# MCU.net
KiCad netlist of a schematic drawn in EAGLE
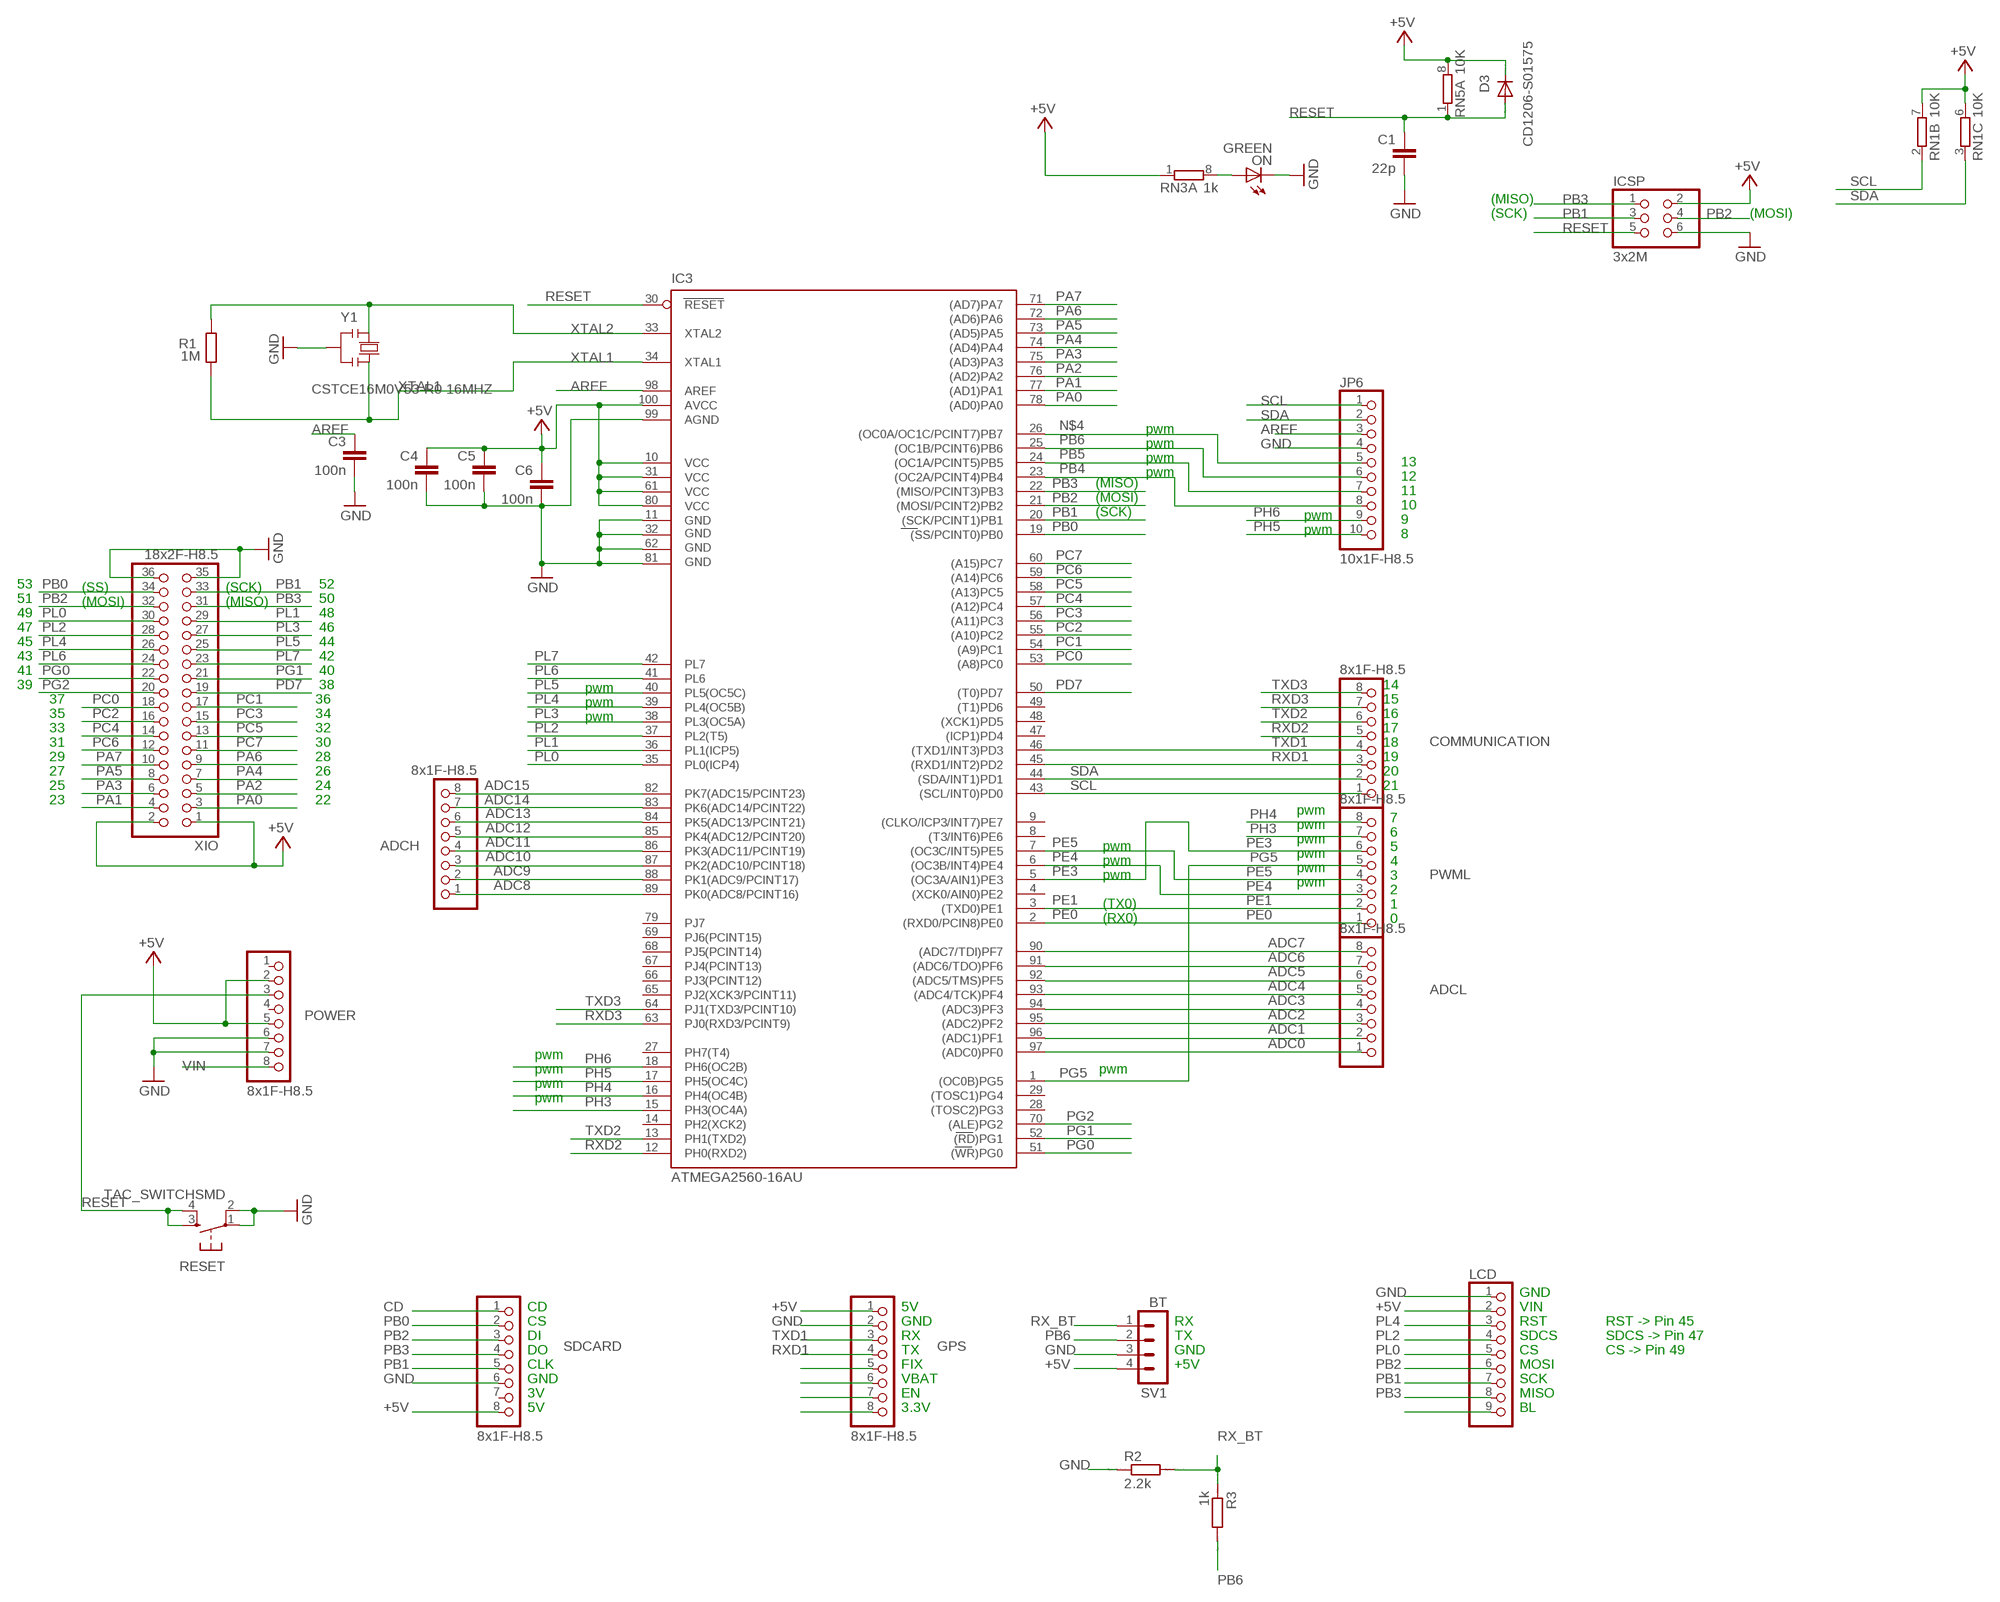
[diagram p0: schematic, sheet 1]

(export (version "E")
  (design (tool "Eeschema 10.0.6"))
  (components
    (comp (ref "ADCH")
      (value "8x1F-H8.5")
      (footprint "eagle-import:1X08")
      (libsource (lib "eagle-import") (part "PINHD-1X8"))
    )
    (comp (ref "ADCL")
      (value "8x1F-H8.5")
      (footprint "eagle-import:1X08")
      (libsource (lib "eagle-import") (part "PINHD-1X8"))
    )
    (comp (ref "C1")
      (value "22p")
      (footprint "eagle-import:C0603-ROUND")
      (libsource (lib "eagle-import") (part "C-EU0603-RND"))
    )
    (comp (ref "C3")
      (value "100n")
      (footprint "eagle-import:C0603-ROUND")
      (libsource (lib "eagle-import") (part "C-EU0603-RND"))
    )
    (comp (ref "C4")
      (value "100n")
      (footprint "eagle-import:C0603-ROUND")
      (libsource (lib "eagle-import") (part "C-EU0603-RND"))
    )
    (comp (ref "C5")
      (value "100n")
      (footprint "eagle-import:C0603-ROUND")
      (libsource (lib "eagle-import") (part "C-EU0603-RND"))
    )
    (comp (ref "C6")
      (value "100n")
      (footprint "eagle-import:C0603-ROUND")
      (libsource (lib "eagle-import") (part "C-EU0603-RND"))
    )
    (comp (ref "COMMUNICATION")
      (value "8x1F-H8.5")
      (footprint "eagle-import:1X08")
      (libsource (lib "eagle-import") (part "PINHD-1X8"))
    )
    (comp (ref "D3")
      (value "CD1206-S01575")
      (footprint "eagle-import:MINIMELF")
      (libsource (lib "eagle-import") (part "DIODE-MINIMELF"))
    )
    (comp (ref "GPS")
      (value "8x1F-H8.5")
      (footprint "eagle-import:1X08")
      (libsource (lib "eagle-import") (part "PINHD-1X8"))
    )
    (comp (ref "IC3")
      (value "ATMEGA2560-16AU")
      (footprint "eagle-import:TQFP100")
      (libsource (lib "eagle-import") (part "ATMEGA2560AU2560-16"))
    )
    (comp (ref "ICSP")
      (value "3x2M")
      (footprint "eagle-import:2X03")
      (libsource (lib "eagle-import") (part "PINHD-2X3"))
    )
    (comp (ref "JP6")
      (value "10x1F-H8.5")
      (footprint "eagle-import:1X10")
      (libsource (lib "eagle-import") (part "PINHD-1X10_ARD"))
    )
    (comp (ref "LCD")
      (value "PINHD-1X9")
      (footprint "eagle-import:1X09")
      (libsource (lib "eagle-import") (part "PINHD-1X9"))
    )
    (comp (ref "ON")
      (value "GREEN")
      (footprint "eagle-import:CHIP-LED0805")
      (libsource (lib "eagle-import") (part "LEDCHIP-LED0805"))
    )
    (comp (ref "POWER")
      (value "8x1F-H8.5")
      (footprint "eagle-import:1X08")
      (libsource (lib "eagle-import") (part "PINHD-1X8"))
    )
    (comp (ref "PWML")
      (value "8x1F-H8.5")
      (footprint "eagle-import:1X08")
      (libsource (lib "eagle-import") (part "PINHD-1X8"))
    )
    (comp (ref "R1")
      (value "1M")
      (footprint "eagle-import:R0603-ROUND")
      (libsource (lib "eagle-import") (part "R-EU_R0603"))
    )
    (comp (ref "R2")
      (value "2.2k")
      (footprint "eagle-import:R0603")
      (libsource (lib "eagle-import") (part "resistor_R-EU_R0603"))
    )
    (comp (ref "R3")
      (value "1k")
      (footprint "eagle-import:R0603")
      (libsource (lib "eagle-import") (part "resistor_R-EU_R0603"))
    )
    (comp (ref "RESET")
      (value "TAC_SWITCHSMD")
      (footprint "eagle-import:TACTILE-SWITCH-SMD")
      (libsource (lib "eagle-import") (part "TAC_SWITCHSMD"))
    )
    (comp (ref "RN1")
      (value "10K")
      (footprint "eagle-import:CAT16")
      (libsource (lib "eagle-import") (part "4R-NCAT16"))
    )
    (comp (ref "RN3")
      (value "1k")
      (footprint "eagle-import:CAY16")
      (libsource (lib "eagle-import") (part "4R-NCAY16"))
    )
    (comp (ref "RN5")
      (value "10K")
      (footprint "eagle-import:CAT16")
      (libsource (lib "eagle-import") (part "4R-NCAT16"))
    )
    (comp (ref "SDCARD")
      (value "8x1F-H8.5")
      (footprint "eagle-import:1X08")
      (libsource (lib "eagle-import") (part "PINHD-1X8"))
    )
    (comp (ref "SV1")
      (value "BT")
      (footprint "eagle-import:MA04-1")
      (libsource (lib "eagle-import") (part "MA04-1"))
    )
    (comp (ref "XIO")
      (value "18x2F-H8.5")
      (footprint "eagle-import:2X18")
      (libsource (lib "eagle-import") (part "PINHD-2X18"))
    )
    (comp (ref "Y1")
      (value "CSTCE16M0V53-R0 16MHZ")
      (footprint "eagle-import:RESONATOR")
      (libsource (lib "eagle-import") (part "RESONATORMU"))
    )
  )
  (nets
    (net (code "1") (name "+5V") (class "Default")
      (node (ref "C4") (pin "1") (pinfunction "1_1") (pintype "passive"))
      (node (ref "C5") (pin "1") (pinfunction "1_1") (pintype "passive"))
      (node (ref "C6") (pin "1") (pinfunction "1_1") (pintype "passive"))
      (node (ref "D3") (pin "C") (pinfunction "C_C") (pintype "passive"))
      (node (ref "GPS") (pin "1") (pinfunction "1_1") (pintype "passive"))
      (node (ref "IC3") (pin "10") (pinfunction "VCC_10") (pintype "power_in"))
      (node (ref "IC3") (pin "100") (pinfunction "AVCC_100") (pintype "power_in"))
      (node (ref "IC3") (pin "31") (pinfunction "VCC1_31") (pintype "power_in"))
      (node (ref "IC3") (pin "61") (pinfunction "VCC2_61") (pintype "power_in"))
      (node (ref "IC3") (pin "80") (pinfunction "VCC3_80") (pintype "power_in"))
      (node (ref "ICSP") (pin "2") (pinfunction "2_2") (pintype "passive"))
      (node (ref "LCD") (pin "2") (pinfunction "2_2") (pintype "passive"))
      (node (ref "POWER") (pin "2") (pinfunction "2_2") (pintype "passive"))
      (node (ref "POWER") (pin "5") (pinfunction "5_5") (pintype "passive"))
      (node (ref "RN1") (pin "6") (pinfunction "2_6") (pintype "passive"))
      (node (ref "RN1") (pin "7") (pinfunction "2_7") (pintype "passive"))
      (node (ref "RN3") (pin "1") (pinfunction "1_1") (pintype "passive"))
      (node (ref "RN5") (pin "8") (pinfunction "2_8") (pintype "passive"))
      (node (ref "SDCARD") (pin "8") (pinfunction "8_8") (pintype "passive"))
      (node (ref "SV1") (pin "4") (pinfunction "4_4") (pintype "passive"))
      (node (ref "XIO") (pin "1") (pinfunction "1_1") (pintype "passive"))
      (node (ref "XIO") (pin "2") (pinfunction "2_2") (pintype "passive"))
    )
    (net (code "2") (name "/ADC0") (class "Default")
      (node (ref "ADCL") (pin "1") (pinfunction "1_1") (pintype "passive"))
      (node (ref "IC3") (pin "97") (pinfunction "(ADC0)PF0_97") (pintype "bidirectional"))
    )
    (net (code "3") (name "/ADC1") (class "Default")
      (node (ref "ADCL") (pin "2") (pinfunction "2_2") (pintype "passive"))
      (node (ref "IC3") (pin "96") (pinfunction "(ADC1)PF1_96") (pintype "bidirectional"))
    )
    (net (code "4") (name "/ADC2") (class "Default")
      (node (ref "ADCL") (pin "3") (pinfunction "3_3") (pintype "passive"))
      (node (ref "IC3") (pin "95") (pinfunction "(ADC2)PF2_95") (pintype "bidirectional"))
    )
    (net (code "5") (name "/ADC3") (class "Default")
      (node (ref "ADCL") (pin "4") (pinfunction "4_4") (pintype "passive"))
      (node (ref "IC3") (pin "94") (pinfunction "(ADC3)PF3_94") (pintype "bidirectional"))
    )
    (net (code "6") (name "/ADC4") (class "Default")
      (node (ref "ADCL") (pin "5") (pinfunction "5_5") (pintype "passive"))
      (node (ref "IC3") (pin "93") (pinfunction "(ADC4/TCK)PF4_93") (pintype "bidirectional"))
    )
    (net (code "7") (name "/ADC5") (class "Default")
      (node (ref "ADCL") (pin "6") (pinfunction "6_6") (pintype "passive"))
      (node (ref "IC3") (pin "92") (pinfunction "(ADC5/TMS)PF5_92") (pintype "bidirectional"))
    )
    (net (code "8") (name "/ADC6") (class "Default")
      (node (ref "ADCL") (pin "7") (pinfunction "7_7") (pintype "passive"))
      (node (ref "IC3") (pin "91") (pinfunction "(ADC6/TDO)PF6_91") (pintype "bidirectional"))
    )
    (net (code "9") (name "/ADC7") (class "Default")
      (node (ref "ADCL") (pin "8") (pinfunction "8_8") (pintype "passive"))
      (node (ref "IC3") (pin "90") (pinfunction "(ADC7/TDI)PF7_90") (pintype "bidirectional"))
    )
    (net (code "10") (name "/ADC8") (class "Default")
      (node (ref "ADCH") (pin "1") (pinfunction "1_1") (pintype "passive"))
      (node (ref "IC3") (pin "89") (pinfunction "PK0(ADC8/PCINT16)_89") (pintype "bidirectional"))
    )
    (net (code "11") (name "/ADC9") (class "Default")
      (node (ref "ADCH") (pin "2") (pinfunction "2_2") (pintype "passive"))
      (node (ref "IC3") (pin "88") (pinfunction "PK1(ADC9/PCINT17)_88") (pintype "bidirectional"))
    )
    (net (code "12") (name "/ADC10") (class "Default")
      (node (ref "ADCH") (pin "3") (pinfunction "3_3") (pintype "passive"))
      (node (ref "IC3") (pin "87") (pinfunction "PK2(ADC10/PCINT18)_87") (pintype "bidirectional"))
    )
    (net (code "13") (name "/ADC11") (class "Default")
      (node (ref "ADCH") (pin "4") (pinfunction "4_4") (pintype "passive"))
      (node (ref "IC3") (pin "86") (pinfunction "PK3(ADC11/PCINT19)_86") (pintype "bidirectional"))
    )
    (net (code "14") (name "/ADC12") (class "Default")
      (node (ref "ADCH") (pin "5") (pinfunction "5_5") (pintype "passive"))
      (node (ref "IC3") (pin "85") (pinfunction "PK4(ADC12/PCINT20)_85") (pintype "bidirectional"))
    )
    (net (code "15") (name "/ADC13") (class "Default")
      (node (ref "ADCH") (pin "6") (pinfunction "6_6") (pintype "passive"))
      (node (ref "IC3") (pin "84") (pinfunction "PK5(ADC13/PCINT21)_84") (pintype "bidirectional"))
    )
    (net (code "16") (name "/ADC14") (class "Default")
      (node (ref "ADCH") (pin "7") (pinfunction "7_7") (pintype "passive"))
      (node (ref "IC3") (pin "83") (pinfunction "PK6(ADC14/PCINT22)_83") (pintype "bidirectional"))
    )
    (net (code "17") (name "/ADC15") (class "Default")
      (node (ref "ADCH") (pin "8") (pinfunction "8_8") (pintype "passive"))
      (node (ref "IC3") (pin "82") (pinfunction "PK7(ADC15/PCINT23)_82") (pintype "bidirectional"))
    )
    (net (code "18") (name "/AREF") (class "Default")
      (node (ref "C3") (pin "1") (pinfunction "1_1") (pintype "passive"))
      (node (ref "IC3") (pin "98") (pinfunction "AREF_98") (pintype "bidirectional"))
      (node (ref "JP6") (pin "3") (pinfunction "3_3") (pintype "passive"))
    )
    (net (code "19") (name "/CD") (class "Default")
      (node (ref "SDCARD") (pin "1") (pinfunction "1_1") (pintype "passive"))
    )
    (net (code "20") (name "/N$4") (class "Default")
      (node (ref "IC3") (pin "26") (pinfunction "(OC0A/OC1C/PCINT7)PB7_26") (pintype "bidirectional"))
      (node (ref "JP6") (pin "5") (pinfunction "5_5") (pintype "passive"))
    )
    (net (code "21") (name "/PA0") (class "Default")
      (node (ref "IC3") (pin "78") (pinfunction "(AD0)PA0_78") (pintype "bidirectional"))
      (node (ref "XIO") (pin "3") (pinfunction "3_3") (pintype "passive"))
    )
    (net (code "22") (name "/PA1") (class "Default")
      (node (ref "IC3") (pin "77") (pinfunction "(AD1)PA1_77") (pintype "bidirectional"))
      (node (ref "XIO") (pin "4") (pinfunction "4_4") (pintype "passive"))
    )
    (net (code "23") (name "/PA2") (class "Default")
      (node (ref "IC3") (pin "76") (pinfunction "(AD2)PA2_76") (pintype "bidirectional"))
      (node (ref "XIO") (pin "5") (pinfunction "5_5") (pintype "passive"))
    )
    (net (code "24") (name "/PA3") (class "Default")
      (node (ref "IC3") (pin "75") (pinfunction "(AD3)PA3_75") (pintype "bidirectional"))
      (node (ref "XIO") (pin "6") (pinfunction "6_6") (pintype "passive"))
    )
    (net (code "25") (name "/PA4") (class "Default")
      (node (ref "IC3") (pin "74") (pinfunction "(AD4)PA4_74") (pintype "bidirectional"))
      (node (ref "XIO") (pin "7") (pinfunction "7_7") (pintype "passive"))
    )
    (net (code "26") (name "/PA5") (class "Default")
      (node (ref "IC3") (pin "73") (pinfunction "(AD5)PA5_73") (pintype "bidirectional"))
      (node (ref "XIO") (pin "8") (pinfunction "8_8") (pintype "passive"))
    )
    (net (code "27") (name "/PA6") (class "Default")
      (node (ref "IC3") (pin "72") (pinfunction "(AD6)PA6_72") (pintype "bidirectional"))
      (node (ref "XIO") (pin "9") (pinfunction "9_9") (pintype "passive"))
    )
    (net (code "28") (name "/PA7") (class "Default")
      (node (ref "IC3") (pin "71") (pinfunction "(AD7)PA7_71") (pintype "bidirectional"))
      (node (ref "XIO") (pin "10") (pinfunction "10_10") (pintype "passive"))
    )
    (net (code "29") (name "/PB0") (class "Default")
      (node (ref "IC3") (pin "19") (pinfunction "(SS/PCINT0)PB0_19") (pintype "bidirectional"))
      (node (ref "SDCARD") (pin "2") (pinfunction "2_2") (pintype "passive"))
      (node (ref "XIO") (pin "34") (pinfunction "34_34") (pintype "passive"))
    )
    (net (code "30") (name "/PB1") (class "Default")
      (node (ref "IC3") (pin "20") (pinfunction "(SCK/PCINT1)PB1_20") (pintype "bidirectional"))
      (node (ref "ICSP") (pin "3") (pinfunction "3_3") (pintype "passive"))
      (node (ref "LCD") (pin "7") (pinfunction "7_7") (pintype "passive"))
      (node (ref "SDCARD") (pin "5") (pinfunction "5_5") (pintype "passive"))
      (node (ref "XIO") (pin "33") (pinfunction "33_33") (pintype "passive"))
    )
    (net (code "31") (name "/PB2") (class "Default")
      (node (ref "IC3") (pin "21") (pinfunction "(MOSI/PCINT2)PB2_21") (pintype "bidirectional"))
      (node (ref "ICSP") (pin "4") (pinfunction "4_4") (pintype "passive"))
      (node (ref "LCD") (pin "6") (pinfunction "6_6") (pintype "passive"))
      (node (ref "SDCARD") (pin "3") (pinfunction "3_3") (pintype "passive"))
      (node (ref "XIO") (pin "32") (pinfunction "32_32") (pintype "passive"))
    )
    (net (code "32") (name "/PB3") (class "Default")
      (node (ref "IC3") (pin "22") (pinfunction "(MISO/PCINT3)PB3_22") (pintype "bidirectional"))
      (node (ref "ICSP") (pin "1") (pinfunction "1_1") (pintype "passive"))
      (node (ref "LCD") (pin "8") (pinfunction "8_8") (pintype "passive"))
      (node (ref "SDCARD") (pin "4") (pinfunction "4_4") (pintype "passive"))
      (node (ref "XIO") (pin "31") (pinfunction "31_31") (pintype "passive"))
    )
    (net (code "33") (name "/PB4") (class "Default")
      (node (ref "IC3") (pin "23") (pinfunction "(OC2A/PCINT4)PB4_23") (pintype "bidirectional"))
      (node (ref "JP6") (pin "8") (pinfunction "8_8") (pintype "passive"))
    )
    (net (code "34") (name "/PB5") (class "Default")
      (node (ref "IC3") (pin "24") (pinfunction "(OC1A/PCINT5)PB5_24") (pintype "bidirectional"))
      (node (ref "JP6") (pin "7") (pinfunction "7_7") (pintype "passive"))
    )
    (net (code "35") (name "/PB6") (class "Default")
      (node (ref "IC3") (pin "25") (pinfunction "(OC1B/PCINT6)PB6_25") (pintype "bidirectional"))
      (node (ref "JP6") (pin "6") (pinfunction "6_6") (pintype "passive"))
      (node (ref "R3") (pin "2") (pinfunction "2_2") (pintype "passive"))
      (node (ref "SV1") (pin "2") (pinfunction "2_2") (pintype "passive"))
    )
    (net (code "36") (name "/PC0") (class "Default")
      (node (ref "IC3") (pin "53") (pinfunction "(A8)PC0_53") (pintype "bidirectional"))
      (node (ref "XIO") (pin "18") (pinfunction "18_18") (pintype "passive"))
    )
    (net (code "37") (name "/PC1") (class "Default")
      (node (ref "IC3") (pin "54") (pinfunction "(A9)PC1_54") (pintype "bidirectional"))
      (node (ref "XIO") (pin "17") (pinfunction "17_17") (pintype "passive"))
    )
    (net (code "38") (name "/PC2") (class "Default")
      (node (ref "IC3") (pin "55") (pinfunction "(A10)PC2_55") (pintype "bidirectional"))
      (node (ref "XIO") (pin "16") (pinfunction "16_16") (pintype "passive"))
    )
    (net (code "39") (name "/PC3") (class "Default")
      (node (ref "IC3") (pin "56") (pinfunction "(A11)PC3_56") (pintype "bidirectional"))
      (node (ref "XIO") (pin "15") (pinfunction "15_15") (pintype "passive"))
    )
    (net (code "40") (name "/PC4") (class "Default")
      (node (ref "IC3") (pin "57") (pinfunction "(A12)PC4_57") (pintype "bidirectional"))
      (node (ref "XIO") (pin "14") (pinfunction "14_14") (pintype "passive"))
    )
    (net (code "41") (name "/PC5") (class "Default")
      (node (ref "IC3") (pin "58") (pinfunction "(A13)PC5_58") (pintype "bidirectional"))
      (node (ref "XIO") (pin "13") (pinfunction "13_13") (pintype "passive"))
    )
    (net (code "42") (name "/PC6") (class "Default")
      (node (ref "IC3") (pin "59") (pinfunction "(A14)PC6_59") (pintype "bidirectional"))
      (node (ref "XIO") (pin "12") (pinfunction "12_12") (pintype "passive"))
    )
    (net (code "43") (name "/PC7") (class "Default")
      (node (ref "IC3") (pin "60") (pinfunction "(A15)PC7_60") (pintype "bidirectional"))
      (node (ref "XIO") (pin "11") (pinfunction "11_11") (pintype "passive"))
    )
    (net (code "44") (name "/PD7") (class "Default")
      (node (ref "IC3") (pin "50") (pinfunction "(T0)PD7_50") (pintype "bidirectional"))
      (node (ref "XIO") (pin "19") (pinfunction "19_19") (pintype "passive"))
    )
    (net (code "45") (name "/PE0") (class "Default")
      (node (ref "IC3") (pin "2") (pinfunction "(RXD0/PCIN8)PE0_2") (pintype "bidirectional"))
      (node (ref "PWML") (pin "1") (pinfunction "1_1") (pintype "passive"))
    )
    (net (code "46") (name "/PE1") (class "Default")
      (node (ref "IC3") (pin "3") (pinfunction "(TXD0)PE1_3") (pintype "bidirectional"))
      (node (ref "PWML") (pin "2") (pinfunction "2_2") (pintype "passive"))
    )
    (net (code "47") (name "/PE3") (class "Default")
      (node (ref "IC3") (pin "5") (pinfunction "(OC3A/AIN1)PE3_5") (pintype "bidirectional"))
      (node (ref "PWML") (pin "6") (pinfunction "6_6") (pintype "passive"))
    )
    (net (code "48") (name "/PE4") (class "Default")
      (node (ref "IC3") (pin "6") (pinfunction "(OC3B/INT4)PE4_6") (pintype "bidirectional"))
      (node (ref "PWML") (pin "3") (pinfunction "3_3") (pintype "passive"))
    )
    (net (code "49") (name "/PE5") (class "Default")
      (node (ref "IC3") (pin "7") (pinfunction "(OC3C/INT5)PE5_7") (pintype "bidirectional"))
      (node (ref "PWML") (pin "4") (pinfunction "4_4") (pintype "passive"))
    )
    (net (code "50") (name "/PG0") (class "Default")
      (node (ref "IC3") (pin "51") (pinfunction "(WR)PG0_51") (pintype "bidirectional"))
      (node (ref "XIO") (pin "22") (pinfunction "22_22") (pintype "passive"))
    )
    (net (code "51") (name "/PG1") (class "Default")
      (node (ref "IC3") (pin "52") (pinfunction "(RD)PG1_52") (pintype "bidirectional"))
      (node (ref "XIO") (pin "21") (pinfunction "21_21") (pintype "passive"))
    )
    (net (code "52") (name "/PG2") (class "Default")
      (node (ref "IC3") (pin "70") (pinfunction "(ALE)PG2_70") (pintype "bidirectional"))
      (node (ref "XIO") (pin "20") (pinfunction "20_20") (pintype "passive"))
    )
    (net (code "53") (name "/PG5") (class "Default")
      (node (ref "IC3") (pin "1") (pinfunction "(OC0B)PG5_1") (pintype "bidirectional"))
      (node (ref "PWML") (pin "5") (pinfunction "5_5") (pintype "passive"))
    )
    (net (code "54") (name "/PH3") (class "Default")
      (node (ref "IC3") (pin "15") (pinfunction "PH3(OC4A)_15") (pintype "bidirectional"))
      (node (ref "PWML") (pin "7") (pinfunction "7_7") (pintype "passive"))
    )
    (net (code "55") (name "/PH4") (class "Default")
      (node (ref "IC3") (pin "16") (pinfunction "PH4(OC4B)_16") (pintype "bidirectional"))
      (node (ref "PWML") (pin "8") (pinfunction "8_8") (pintype "passive"))
    )
    (net (code "56") (name "/PH5") (class "Default")
      (node (ref "IC3") (pin "17") (pinfunction "PH5(OC4C)_17") (pintype "bidirectional"))
      (node (ref "JP6") (pin "10") (pinfunction "10_10") (pintype "passive"))
    )
    (net (code "57") (name "/PH6") (class "Default")
      (node (ref "IC3") (pin "18") (pinfunction "PH6(OC2B)_18") (pintype "bidirectional"))
      (node (ref "JP6") (pin "9") (pinfunction "9_9") (pintype "passive"))
    )
    (net (code "58") (name "/PL0") (class "Default")
      (node (ref "IC3") (pin "35") (pinfunction "PL0(ICP4)_35") (pintype "bidirectional"))
      (node (ref "LCD") (pin "5") (pinfunction "5_5") (pintype "passive"))
      (node (ref "XIO") (pin "30") (pinfunction "30_30") (pintype "passive"))
    )
    (net (code "59") (name "/PL1") (class "Default")
      (node (ref "IC3") (pin "36") (pinfunction "PL1(ICP5)_36") (pintype "bidirectional"))
      (node (ref "XIO") (pin "29") (pinfunction "29_29") (pintype "passive"))
    )
    (net (code "60") (name "/PL2") (class "Default")
      (node (ref "IC3") (pin "37") (pinfunction "PL2(T5)_37") (pintype "bidirectional"))
      (node (ref "LCD") (pin "4") (pinfunction "4_4") (pintype "passive"))
      (node (ref "XIO") (pin "28") (pinfunction "28_28") (pintype "passive"))
    )
    (net (code "61") (name "/PL3") (class "Default")
      (node (ref "IC3") (pin "38") (pinfunction "PL3(OC5A)_38") (pintype "bidirectional"))
      (node (ref "XIO") (pin "27") (pinfunction "27_27") (pintype "passive"))
    )
    (net (code "62") (name "/PL4") (class "Default")
      (node (ref "IC3") (pin "39") (pinfunction "PL4(OC5B)_39") (pintype "bidirectional"))
      (node (ref "LCD") (pin "3") (pinfunction "3_3") (pintype "passive"))
      (node (ref "XIO") (pin "26") (pinfunction "26_26") (pintype "passive"))
    )
    (net (code "63") (name "/PL5") (class "Default")
      (node (ref "IC3") (pin "40") (pinfunction "PL5(OC5C)_40") (pintype "bidirectional"))
      (node (ref "XIO") (pin "25") (pinfunction "25_25") (pintype "passive"))
    )
    (net (code "64") (name "/PL6") (class "Default")
      (node (ref "IC3") (pin "41") (pinfunction "PL6_41") (pintype "bidirectional"))
      (node (ref "XIO") (pin "24") (pinfunction "24_24") (pintype "passive"))
    )
    (net (code "65") (name "/PL7") (class "Default")
      (node (ref "IC3") (pin "42") (pinfunction "PL7_42") (pintype "bidirectional"))
      (node (ref "XIO") (pin "23") (pinfunction "23_23") (pintype "passive"))
    )
    (net (code "66") (name "/RESET") (class "Default")
      (node (ref "C1") (pin "1") (pinfunction "1_1") (pintype "passive"))
      (node (ref "D3") (pin "A") (pinfunction "A_A") (pintype "passive"))
      (node (ref "IC3") (pin "30") (pinfunction "RESET_30") (pintype "input"))
      (node (ref "ICSP") (pin "5") (pinfunction "5_5") (pintype "passive"))
      (node (ref "POWER") (pin "3") (pinfunction "3_3") (pintype "passive"))
      (node (ref "RESET") (pin "3") (pinfunction "3_3") (pintype "passive"))
      (node (ref "RESET") (pin "4") (pinfunction "4_4") (pintype "passive"))
      (node (ref "RN5") (pin "1") (pinfunction "1_1") (pintype "passive"))
    )
    (net (code "67") (name "/RXD1") (class "Default")
      (node (ref "COMMUNICATION") (pin "3") (pinfunction "3_3") (pintype "passive"))
      (node (ref "GPS") (pin "4") (pinfunction "4_4") (pintype "passive"))
      (node (ref "IC3") (pin "45") (pinfunction "(RXD1/INT2)PD2_45") (pintype "bidirectional"))
    )
    (net (code "68") (name "/RXD2") (class "Default")
      (node (ref "COMMUNICATION") (pin "5") (pinfunction "5_5") (pintype "passive"))
      (node (ref "IC3") (pin "12") (pinfunction "PH0(RXD2)_12") (pintype "bidirectional"))
    )
    (net (code "69") (name "/RXD3") (class "Default")
      (node (ref "COMMUNICATION") (pin "7") (pinfunction "7_7") (pintype "passive"))
      (node (ref "IC3") (pin "63") (pinfunction "PJ0(RXD3/PCINT9)_63") (pintype "bidirectional"))
    )
    (net (code "70") (name "/RX_BT") (class "Default")
      (node (ref "R2") (pin "2") (pinfunction "2_2") (pintype "passive"))
      (node (ref "R3") (pin "1") (pinfunction "1_1") (pintype "passive"))
      (node (ref "SV1") (pin "1") (pinfunction "1_1") (pintype "passive"))
    )
    (net (code "71") (name "/SCL") (class "Default")
      (node (ref "COMMUNICATION") (pin "1") (pinfunction "1_1") (pintype "passive"))
      (node (ref "IC3") (pin "43") (pinfunction "(SCL/INT0)PD0_43") (pintype "bidirectional"))
      (node (ref "JP6") (pin "1") (pinfunction "1_1") (pintype "passive"))
      (node (ref "RN1") (pin "2") (pinfunction "1_2") (pintype "passive"))
    )
    (net (code "72") (name "/SDA") (class "Default")
      (node (ref "COMMUNICATION") (pin "2") (pinfunction "2_2") (pintype "passive"))
      (node (ref "IC3") (pin "44") (pinfunction "(SDA/INT1)PD1_44") (pintype "bidirectional"))
      (node (ref "JP6") (pin "2") (pinfunction "2_2") (pintype "passive"))
      (node (ref "RN1") (pin "3") (pinfunction "1_3") (pintype "passive"))
    )
    (net (code "73") (name "/TXD1") (class "Default")
      (node (ref "COMMUNICATION") (pin "4") (pinfunction "4_4") (pintype "passive"))
      (node (ref "GPS") (pin "3") (pinfunction "3_3") (pintype "passive"))
      (node (ref "IC3") (pin "46") (pinfunction "(TXD1/INT3)PD3_46") (pintype "bidirectional"))
    )
    (net (code "74") (name "/TXD2") (class "Default")
      (node (ref "COMMUNICATION") (pin "6") (pinfunction "6_6") (pintype "passive"))
      (node (ref "IC3") (pin "13") (pinfunction "PH1(TXD2)_13") (pintype "bidirectional"))
    )
    (net (code "75") (name "/TXD3") (class "Default")
      (node (ref "COMMUNICATION") (pin "8") (pinfunction "8_8") (pintype "passive"))
      (node (ref "IC3") (pin "64") (pinfunction "PJ1(TXD3/PCINT10)_64") (pintype "bidirectional"))
    )
    (net (code "76") (name "/VIN") (class "Default")
      (node (ref "POWER") (pin "8") (pinfunction "8_8") (pintype "passive"))
    )
    (net (code "77") (name "/XTAL1") (class "Default")
      (node (ref "IC3") (pin "34") (pinfunction "XTAL1_34") (pintype "input"))
      (node (ref "R1") (pin "1") (pinfunction "1_1") (pintype "passive"))
      (node (ref "Y1") (pin "3") (pinfunction "3_3") (pintype "passive"))
    )
    (net (code "78") (name "/XTAL2") (class "Default")
      (node (ref "IC3") (pin "33") (pinfunction "XTAL2_33") (pintype "output"))
      (node (ref "R1") (pin "2") (pinfunction "2_2") (pintype "passive"))
      (node (ref "Y1") (pin "1") (pinfunction "1_1") (pintype "passive"))
    )
    (net (code "79") (name "GND") (class "Default")
      (node (ref "C1") (pin "2") (pinfunction "2_2") (pintype "passive"))
      (node (ref "C3") (pin "2") (pinfunction "2_2") (pintype "passive"))
      (node (ref "C4") (pin "2") (pinfunction "2_2") (pintype "passive"))
      (node (ref "C5") (pin "2") (pinfunction "2_2") (pintype "passive"))
      (node (ref "C6") (pin "2") (pinfunction "2_2") (pintype "passive"))
      (node (ref "GPS") (pin "2") (pinfunction "2_2") (pintype "passive"))
      (node (ref "IC3") (pin "11") (pinfunction "GND_11") (pintype "power_in"))
      (node (ref "IC3") (pin "32") (pinfunction "GND1_32") (pintype "power_in"))
      (node (ref "IC3") (pin "62") (pinfunction "GND2_62") (pintype "power_in"))
      (node (ref "IC3") (pin "81") (pinfunction "GND3_81") (pintype "power_in"))
      (node (ref "IC3") (pin "99") (pinfunction "AGND_99") (pintype "power_in"))
      (node (ref "ICSP") (pin "6") (pinfunction "6_6") (pintype "passive"))
      (node (ref "JP6") (pin "4") (pinfunction "4_4") (pintype "passive"))
      (node (ref "LCD") (pin "1") (pinfunction "1_1") (pintype "passive"))
      (node (ref "ON") (pin "C") (pinfunction "C_C") (pintype "passive"))
      (node (ref "POWER") (pin "6") (pinfunction "6_6") (pintype "passive"))
      (node (ref "POWER") (pin "7") (pinfunction "7_7") (pintype "passive"))
      (node (ref "R2") (pin "1") (pinfunction "1_1") (pintype "passive"))
      (node (ref "RESET") (pin "1") (pinfunction "1_1") (pintype "passive"))
      (node (ref "RESET") (pin "2") (pinfunction "2_2") (pintype "passive"))
      (node (ref "SDCARD") (pin "6") (pinfunction "6_6") (pintype "passive"))
      (node (ref "SV1") (pin "3") (pinfunction "3_3") (pintype "passive"))
      (node (ref "XIO") (pin "35") (pinfunction "35_35") (pintype "passive"))
      (node (ref "XIO") (pin "36") (pinfunction "36_36") (pintype "passive"))
      (node (ref "Y1") (pin "2") (pinfunction "2_2") (pintype "passive"))
    )
    (net (code "80") (name "Net-(RN3A-2)") (class "Default")
      (node (ref "ON") (pin "A") (pinfunction "A_A") (pintype "passive"))
      (node (ref "RN3") (pin "8") (pinfunction "2_8") (pintype "passive"))
    )
    (net (code "81") (name "unconnected-(GPS-Pad5)") (class "Default")
      (node (ref "GPS") (pin "5") (pinfunction "5_5") (pintype "passive"))
    )
    (net (code "82") (name "unconnected-(GPS-Pad6)") (class "Default")
      (node (ref "GPS") (pin "6") (pinfunction "6_6") (pintype "passive"))
    )
    (net (code "83") (name "unconnected-(GPS-Pad7)") (class "Default")
      (node (ref "GPS") (pin "7") (pinfunction "7_7") (pintype "passive"))
    )
    (net (code "84") (name "unconnected-(GPS-Pad8)") (class "Default")
      (node (ref "GPS") (pin "8") (pinfunction "8_8") (pintype "passive"))
    )
    (net (code "85") (name "unconnected-(IC3-(CLKO{slash}ICP3{slash}INT7)PE7-Pad9)") (class "Default")
      (node (ref "IC3") (pin "9") (pinfunction "(CLKO/ICP3/INT7)PE7_9") (pintype "bidirectional"))
    )
    (net (code "86") (name "unconnected-(IC3-(ICP1)PD4-Pad47)") (class "Default")
      (node (ref "IC3") (pin "47") (pinfunction "(ICP1)PD4_47") (pintype "bidirectional"))
    )
    (net (code "87") (name "unconnected-(IC3-(T1)PD6-Pad49)") (class "Default")
      (node (ref "IC3") (pin "49") (pinfunction "(T1)PD6_49") (pintype "bidirectional"))
    )
    (net (code "88") (name "unconnected-(IC3-(T3{slash}INT6)PE6-Pad8)") (class "Default")
      (node (ref "IC3") (pin "8") (pinfunction "(T3/INT6)PE6_8") (pintype "bidirectional"))
    )
    (net (code "89") (name "unconnected-(IC3-(TOSC1)PG4-Pad29)") (class "Default")
      (node (ref "IC3") (pin "29") (pinfunction "(TOSC1)PG4_29") (pintype "bidirectional"))
    )
    (net (code "90") (name "unconnected-(IC3-(TOSC2)PG3-Pad28)") (class "Default")
      (node (ref "IC3") (pin "28") (pinfunction "(TOSC2)PG3_28") (pintype "bidirectional"))
    )
    (net (code "91") (name "unconnected-(IC3-(XCK0{slash}AIN0)PE2-Pad4)") (class "Default")
      (node (ref "IC3") (pin "4") (pinfunction "(XCK0/AIN0)PE2_4") (pintype "bidirectional"))
    )
    (net (code "92") (name "unconnected-(IC3-(XCK1)PD5-Pad48)") (class "Default")
      (node (ref "IC3") (pin "48") (pinfunction "(XCK1)PD5_48") (pintype "bidirectional"))
    )
    (net (code "93") (name "unconnected-(IC3-PH2(XCK2)-Pad14)") (class "Default")
      (node (ref "IC3") (pin "14") (pinfunction "PH2(XCK2)_14") (pintype "bidirectional"))
    )
    (net (code "94") (name "unconnected-(IC3-PH7(T4)-Pad27)") (class "Default")
      (node (ref "IC3") (pin "27") (pinfunction "PH7(T4)_27") (pintype "bidirectional"))
    )
    (net (code "95") (name "unconnected-(IC3-PJ2(XCK3{slash}PCINT11)-Pad65)") (class "Default")
      (node (ref "IC3") (pin "65") (pinfunction "PJ2(XCK3/PCINT11)_65") (pintype "bidirectional"))
    )
    (net (code "96") (name "unconnected-(IC3-PJ3(PCINT12)-Pad66)") (class "Default")
      (node (ref "IC3") (pin "66") (pinfunction "PJ3(PCINT12)_66") (pintype "bidirectional"))
    )
    (net (code "97") (name "unconnected-(IC3-PJ4(PCINT13)-Pad67)") (class "Default")
      (node (ref "IC3") (pin "67") (pinfunction "PJ4(PCINT13)_67") (pintype "bidirectional"))
    )
    (net (code "98") (name "unconnected-(IC3-PJ5(PCINT14)-Pad68)") (class "Default")
      (node (ref "IC3") (pin "68") (pinfunction "PJ5(PCINT14)_68") (pintype "bidirectional"))
    )
    (net (code "99") (name "unconnected-(IC3-PJ6(PCINT15)-Pad69)") (class "Default")
      (node (ref "IC3") (pin "69") (pinfunction "PJ6(PCINT15)_69") (pintype "bidirectional"))
    )
    (net (code "100") (name "unconnected-(IC3-PJ7-Pad79)") (class "Default")
      (node (ref "IC3") (pin "79") (pinfunction "PJ7_79") (pintype "bidirectional"))
    )
    (net (code "101") (name "unconnected-(LCD-Pad9)") (class "Default")
      (node (ref "LCD") (pin "9") (pinfunction "9_9") (pintype "passive"))
    )
    (net (code "102") (name "unconnected-(POWER-Pad1)") (class "Default")
      (node (ref "POWER") (pin "1") (pinfunction "1_1") (pintype "passive"))
    )
    (net (code "103") (name "unconnected-(POWER-Pad4)") (class "Default")
      (node (ref "POWER") (pin "4") (pinfunction "4_4") (pintype "passive"))
    )
    (net (code "104") (name "unconnected-(SDCARD-Pad7)") (class "Default")
      (node (ref "SDCARD") (pin "7") (pinfunction "7_7") (pintype "passive"))
    )
  )
)
